# Soldering_Iron_V2.net
KiCad netlist of a schematic drawn in EAGLE
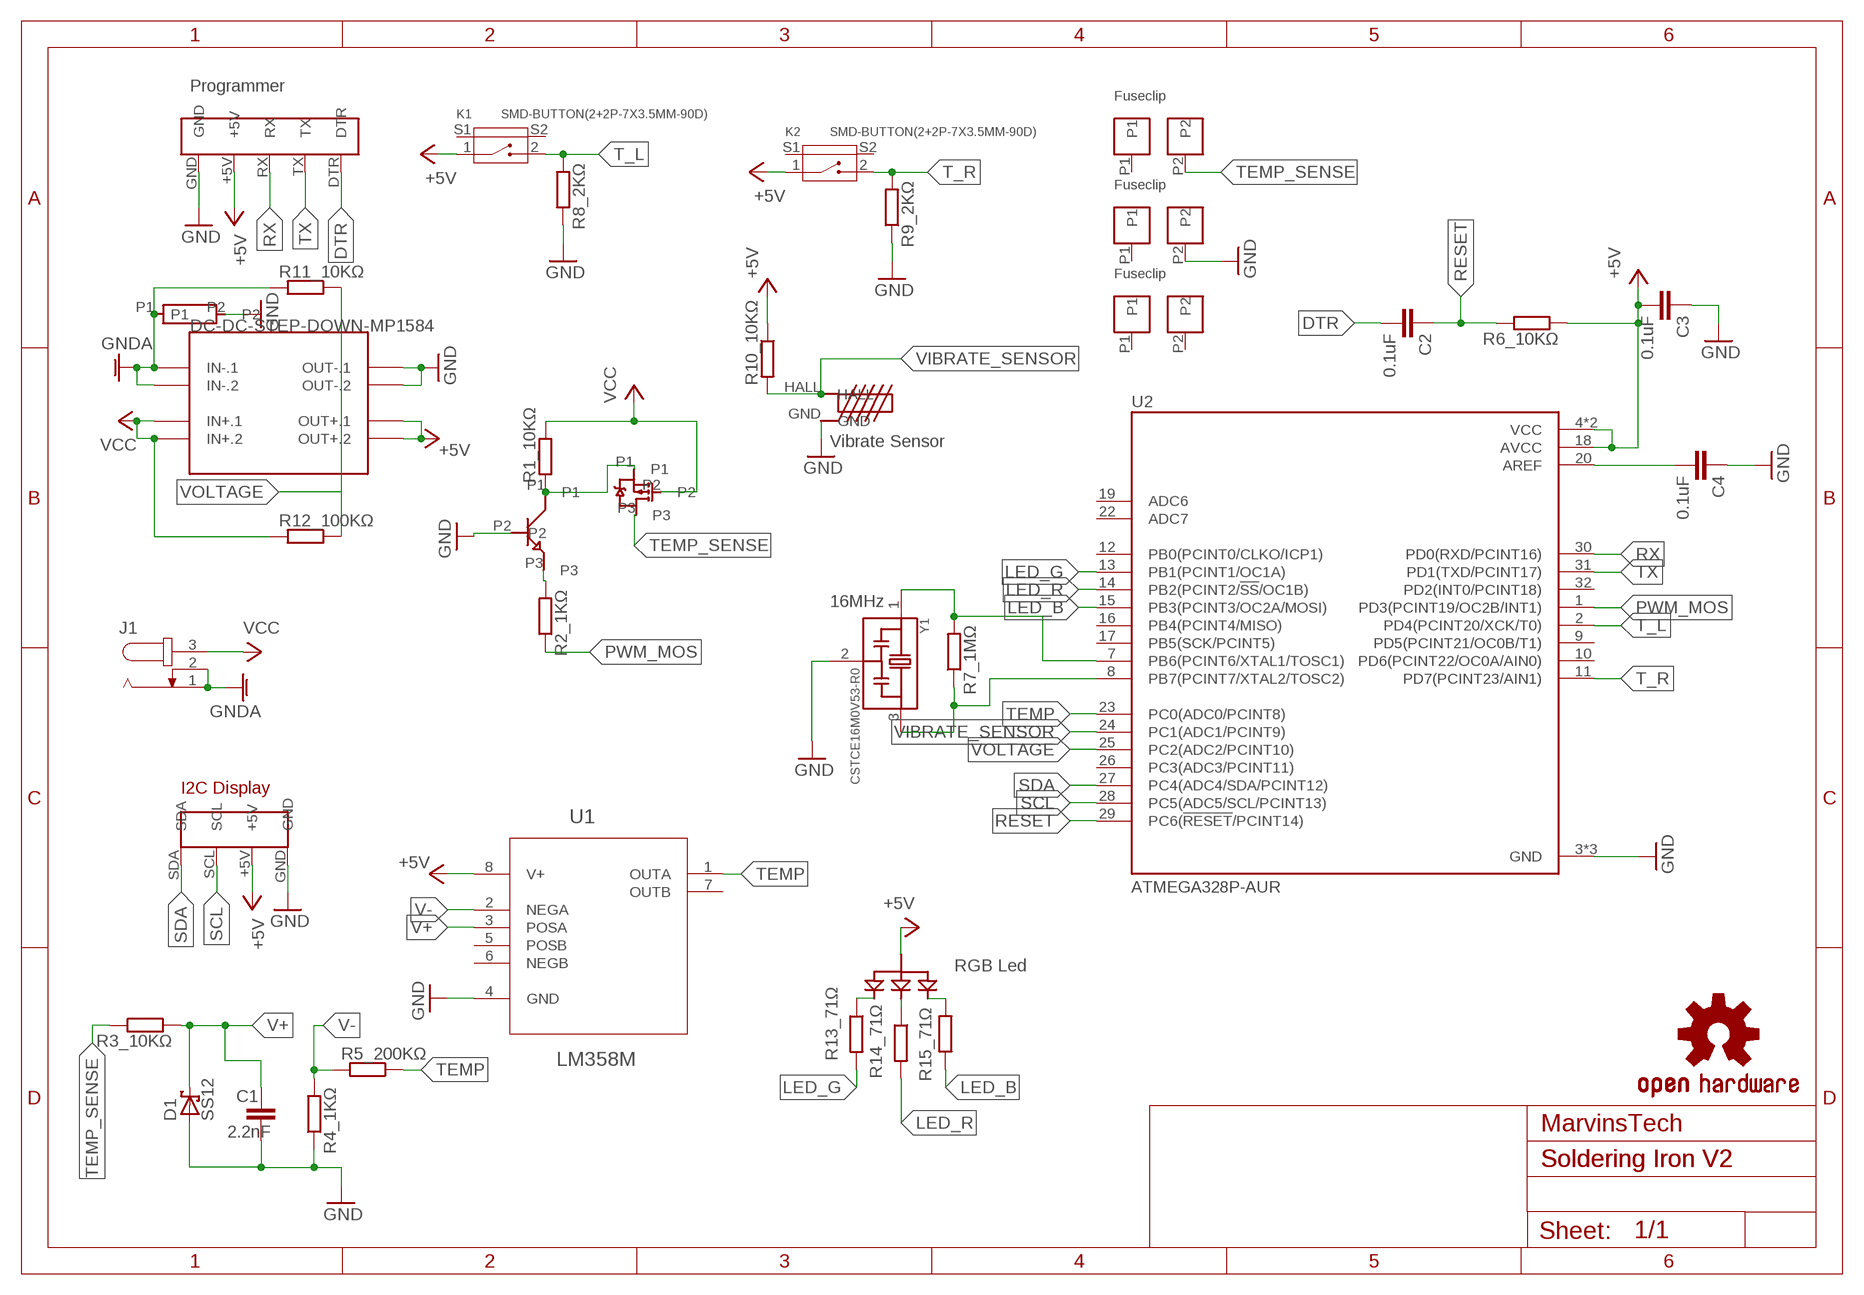
[diagram p0: schematic, sheet 1]

(export (version "E")
  (design (tool "Eeschema 10.0.6"))
  (components
    (comp (ref "C1")
      (value "2.2nF")
      (footprint "eagle-import:0603")
      (libsource (lib "eagle-import") (part "2.2NF/2200PF-0603-50V-10%"))
    )
    (comp (ref "C2")
      (value "0.1uF")
      (footprint "eagle-import:0603")
      (libsource (lib "eagle-import") (part "0.1UF-0603-25V-(+80/-20%)"))
    )
    (comp (ref "C3")
      (value "0.1uF")
      (footprint "eagle-import:0603")
      (libsource (lib "eagle-import") (part "0.1UF-0603-25V-(+80/-20%)"))
    )
    (comp (ref "C4")
      (value "0.1uF")
      (footprint "eagle-import:0603")
      (libsource (lib "eagle-import") (part "0.1UF-0603-25V-(+80/-20%)"))
    )
    (comp (ref "D1")
      (value "SS12")
      (footprint "eagle-import:DO214AC")
      (fields (field (name "MF") "Klein Tools,"))
      (libsource (lib "eagle-import") (part "SS12"))
    )
    (comp (ref "J1")
      (value "JACK-PLUG0")
      (footprint "eagle-import:SPC4077")
      (libsource (lib "eagle-import") (part "JACK-PLUG0"))
    )
    (comp (ref "K1")
      (value "SMD-BUTTON(2+2P-7X3.5MM-90D)")
      (footprint "eagle-import:SW4-SMD-7.0X3.5X3.5MM-90D")
      (fields (field (name "MF") "Best Inc.") (field (name "MP") "TS-1188E"))
      (libsource (lib "eagle-import") (part "SMD-BUTTON(2+2P-7X3.5MM-90D)"))
    )
    (comp (ref "K2")
      (value "SMD-BUTTON(2+2P-7X3.5MM-90D)")
      (footprint "eagle-import:SW4-SMD-7.0X3.5X3.5MM-90D")
      (fields (field (name "MF") "Best Inc.") (field (name "MP") "TS-1188E"))
      (libsource (lib "eagle-import") (part "SMD-BUTTON(2+2P-7X3.5MM-90D)"))
    )
    (comp (ref "R1_10KΩ")
      (value "SMK")
      (footprint "eagle-import:SMK")
      (libsource (lib "eagle-import") (part "SMK"))
    )
    (comp (ref "R2_1KΩ")
      (value "SMK")
      (footprint "eagle-import:SMK")
      (libsource (lib "eagle-import") (part "SMK"))
    )
    (comp (ref "R3_10KΩ")
      (value "SMK")
      (footprint "eagle-import:SMK")
      (libsource (lib "eagle-import") (part "SMK"))
    )
    (comp (ref "R4_1KΩ")
      (value "SMK")
      (footprint "eagle-import:SMK")
      (libsource (lib "eagle-import") (part "SMK"))
    )
    (comp (ref "R5_200KΩ")
      (value "SMK")
      (footprint "eagle-import:SMK")
      (libsource (lib "eagle-import") (part "SMK"))
    )
    (comp (ref "R6_10KΩ")
      (value "SMK")
      (footprint "eagle-import:SMK")
      (libsource (lib "eagle-import") (part "SMK"))
    )
    (comp (ref "R7_1MΩ")
      (value "SMK")
      (footprint "eagle-import:SMK")
      (libsource (lib "eagle-import") (part "SMK"))
    )
    (comp (ref "R8_2KΩ")
      (value "SMK")
      (footprint "eagle-import:SMK")
      (libsource (lib "eagle-import") (part "SMK"))
    )
    (comp (ref "R9_2KΩ")
      (value "SMK")
      (footprint "eagle-import:SMK")
      (libsource (lib "eagle-import") (part "SMK"))
    )
    (comp (ref "R10_10KΩ")
      (value "SMK")
      (footprint "eagle-import:SMK")
      (libsource (lib "eagle-import") (part "SMK"))
    )
    (comp (ref "R11_10KΩ")
      (value "SMK")
      (footprint "eagle-import:SMK")
      (libsource (lib "eagle-import") (part "SMK"))
    )
    (comp (ref "R12_100KΩ")
      (value "SMK")
      (footprint "eagle-import:SMK")
      (libsource (lib "eagle-import") (part "SMK"))
    )
    (comp (ref "R13_71Ω")
      (value "SMK")
      (footprint "eagle-import:SMK")
      (libsource (lib "eagle-import") (part "SMK"))
    )
    (comp (ref "R14_71Ω")
      (value "SMK")
      (footprint "eagle-import:SMK")
      (libsource (lib "eagle-import") (part "SMK"))
    )
    (comp (ref "R15_71Ω")
      (value "SMK")
      (footprint "eagle-import:SMK")
      (libsource (lib "eagle-import") (part "SMK"))
    )
    (comp (ref "U$1")
      (value "DC-DC-STEP-DOWN-MP1584")
      (footprint "eagle-import:DC-DC-STEP-DOWN-MP1584")
      (libsource (lib "eagle-import") (part "DC-DC-STEP-DOWN-MP1584"))
    )
    (comp (ref "U$2")
      (value "IRF4905STRLPBF")
      (footprint "eagle-import:D2PAK-5")
      (libsource (lib "eagle-import") (part "IRF4905STRLPBF"))
    )
    (comp (ref "U$3")
      (value "2SC3356NPNBJT")
      (footprint "eagle-import:TO236")
      (libsource (lib "eagle-import") (part "2SC3356NPNBJT"))
    )
    (comp (ref "U$4")
      (value "I2C_DISPLAY")
      (footprint "eagle-import:I2C_DISPLAY")
      (libsource (lib "eagle-import") (part "I2C_DISPLAY"))
    )
    (comp (ref "U$5")
      (value "VIBRATESENSOR")
      (footprint "eagle-import:VIBRATESENSOR")
      (libsource (lib "eagle-import") (part "VIBRATESENSOR"))
    )
    (comp (ref "U$6")
      (value "FUSECLIPS")
      (footprint "eagle-import:FUSECLIP")
      (libsource (lib "eagle-import") (part "FUSECLIPS"))
    )
    (comp (ref "U$7")
      (value "FUSECLIPS")
      (footprint "eagle-import:FUSECLIP")
      (libsource (lib "eagle-import") (part "FUSECLIPS"))
    )
    (comp (ref "U$8")
      (value "FUSECLIPS")
      (footprint "eagle-import:FUSECLIP")
      (libsource (lib "eagle-import") (part "FUSECLIPS"))
    )
    (comp (ref "U$9")
      (value "SHUNT_RESISTOR1")
      (footprint "eagle-import:RESISTOR1")
      (libsource (lib "eagle-import") (part "SHUNT_RESISTOR1"))
    )
    (comp (ref "U$10")
      (value "RGBLED")
      (footprint "eagle-import:RGBLED")
      (libsource (lib "eagle-import") (part "RGBLED"))
    )
    (comp (ref "U$11")
      (value "PROGRAMMER")
      (footprint "eagle-import:PROGRAMMER")
      (libsource (lib "eagle-import") (part "PROGRAMMER"))
    )
    (comp (ref "U$15")
      (value "OSHW-LOGOS")
      (footprint "eagle-import:OSHW-LOGO-S")
      (libsource (lib "eagle-import") (part "OSHW-LOGOS"))
    )
    (comp (ref "U1")
      (value "LM358M")
      (footprint "eagle-import:SOIC127P620X175-8N")
      (fields (field (name "MF") "ON Semiconductor"))
      (libsource (lib "eagle-import") (part "LM358M"))
    )
    (comp (ref "U2")
      (value "ATMEGA328P-AUR")
      (footprint "eagle-import:QFP80P900X900X120-32N")
      (fields (field (name "MF") "Microchip"))
      (libsource (lib "eagle-import") (part "ATMEGA328P-AUR"))
    )
    (comp (ref "Y1")
      (value "CSTCE16M0V53-R0")
      (footprint "eagle-import:OSC_CSTCE16M0V53-R0")
      (fields (field (name "MF") "Murata"))
      (libsource (lib "eagle-import") (part "CSTCE16M0V53-R0"))
    )
  )
  (nets
    (net (code "1") (name "+5V") (class "Default")
      (node (ref "C3") (pin "2") (pinfunction "2_2") (pintype "passive"))
      (node (ref "K1") (pin "1") (pinfunction "1_1") (pintype "bidirectional"))
      (node (ref "K2") (pin "1") (pinfunction "1_1") (pintype "bidirectional"))
      (node (ref "R10_10KΩ") (pin "1") (pinfunction "1_1") (pintype "passive"))
      (node (ref "R6_10KΩ") (pin "2") (pinfunction "2_2") (pintype "passive"))
      (node (ref "U$1") (pin "OUT+.1") (pinfunction "OUT+.1_OUT+.1") (pintype "bidirectional"))
      (node (ref "U$1") (pin "OUT+.2") (pinfunction "OUT+.2_OUT+.2") (pintype "bidirectional"))
      (node (ref "U$10") (pin "+5V") (pinfunction "+5V_+5V") (pintype "bidirectional"))
      (node (ref "U$11") (pin "+5V") (pinfunction "+5V_+5V") (pintype "bidirectional"))
      (node (ref "U$4") (pin "+5V") (pinfunction "+5V_+5V") (pintype "bidirectional"))
      (node (ref "U1") (pin "8") (pinfunction "V+_8") (pintype "power_in"))
      (node (ref "U2") (pin "18") (pinfunction "AVCC_18") (pintype "power_in"))
      (node (ref "U2") (pin "4") (pinfunction "VCC_4") (pintype "power_in"))
      (node (ref "U2") (pin "6") (pinfunction "VCC_6") (pintype "power_in"))
    )
    (net (code "2") (name "DTR") (class "Default")
      (node (ref "C2") (pin "2") (pinfunction "2_2") (pintype "passive"))
      (node (ref "U$11") (pin "DTR") (pinfunction "DTR_DTR") (pintype "bidirectional"))
    )
    (net (code "3") (name "GND") (class "Default")
      (node (ref "C1") (pin "2") (pinfunction "2_2") (pintype "passive"))
      (node (ref "C3") (pin "1") (pinfunction "1_1") (pintype "passive"))
      (node (ref "C4") (pin "1") (pinfunction "1_1") (pintype "passive"))
      (node (ref "D1") (pin "A") (pinfunction "A_A") (pintype "passive"))
      (node (ref "R4_1KΩ") (pin "1") (pinfunction "1_1") (pintype "passive"))
      (node (ref "R8_2KΩ") (pin "1") (pinfunction "1_1") (pintype "passive"))
      (node (ref "R9_2KΩ") (pin "1") (pinfunction "1_1") (pintype "passive"))
      (node (ref "U$1") (pin "OUT-.1") (pinfunction "OUT-.1_OUT-.1") (pintype "bidirectional"))
      (node (ref "U$1") (pin "OUT-.2") (pinfunction "OUT-.2_OUT-.2") (pintype "bidirectional"))
      (node (ref "U$11") (pin "GND") (pinfunction "GND_GND") (pintype "bidirectional"))
      (node (ref "U$3") (pin "P2") (pinfunction "P2_P2") (pintype "bidirectional"))
      (node (ref "U$4") (pin "GND") (pinfunction "GND_GND") (pintype "bidirectional"))
      (node (ref "U$5") (pin "GND") (pinfunction "GND_GND") (pintype "bidirectional"))
      (node (ref "U$7") (pin "P2") (pinfunction "P2_P2") (pintype "bidirectional"))
      (node (ref "U$9") (pin "P2") (pinfunction "P2_P2") (pintype "bidirectional"))
      (node (ref "U1") (pin "4") (pinfunction "GND_4") (pintype "passive"))
      (node (ref "U2") (pin "21") (pinfunction "GND_21") (pintype "power_in"))
      (node (ref "U2") (pin "3") (pinfunction "GND_3") (pintype "power_in"))
      (node (ref "U2") (pin "5") (pinfunction "GND_5") (pintype "power_in"))
      (node (ref "Y1") (pin "2") (pinfunction "2_2") (pintype "power_in"))
    )
    (net (code "4") (name "GNDA") (class "Default")
      (node (ref "J1") (pin "1") (pinfunction "1_1") (pintype "passive"))
      (node (ref "J1") (pin "2") (pinfunction "2_2") (pintype "passive"))
      (node (ref "R11_10KΩ") (pin "2") (pinfunction "2_2") (pintype "passive"))
      (node (ref "U$1") (pin "IN-.1") (pinfunction "IN-.1_IN-.1") (pintype "bidirectional"))
      (node (ref "U$1") (pin "IN-.2") (pinfunction "IN-.2_IN-.2") (pintype "bidirectional"))
      (node (ref "U$9") (pin "P1") (pinfunction "P1_P1") (pintype "bidirectional"))
    )
    (net (code "5") (name "LED_B") (class "Default")
      (node (ref "R15_71Ω") (pin "1") (pinfunction "1_1") (pintype "passive"))
      (node (ref "U2") (pin "15") (pinfunction "PB3(PCINT3/OC2A/MOSI)_15") (pintype "bidirectional"))
    )
    (net (code "6") (name "LED_G") (class "Default")
      (node (ref "R13_71Ω") (pin "2") (pinfunction "2_2") (pintype "passive"))
      (node (ref "U2") (pin "13") (pinfunction "PB1(PCINT1/OC1A)_13") (pintype "bidirectional"))
    )
    (net (code "7") (name "LED_R") (class "Default")
      (node (ref "R14_71Ω") (pin "2") (pinfunction "2_2") (pintype "passive"))
      (node (ref "U2") (pin "14") (pinfunction "PB2(PCINT2/~{SS}/OC1B)_14") (pintype "bidirectional"))
    )
    (net (code "8") (name "Net-(R1_10KΩ-Pad2)") (class "Default")
      (node (ref "R1_10KΩ") (pin "2") (pinfunction "2_2") (pintype "passive"))
      (node (ref "U$2") (pin "P1") (pinfunction "P1_P1") (pintype "bidirectional"))
      (node (ref "U$3") (pin "P1") (pinfunction "P1_P1") (pintype "bidirectional"))
    )
    (net (code "9") (name "Net-(R2_1KΩ-Pad2)") (class "Default")
      (node (ref "R2_1KΩ") (pin "2") (pinfunction "2_2") (pintype "passive"))
      (node (ref "U$3") (pin "P3") (pinfunction "P3_P3") (pintype "bidirectional"))
    )
    (net (code "10") (name "Net-(R13_71Ω-Pad1)") (class "Default")
      (node (ref "R13_71Ω") (pin "1") (pinfunction "1_1") (pintype "passive"))
      (node (ref "U$10") (pin "P3") (pinfunction "P3_P3") (pintype "bidirectional"))
    )
    (net (code "11") (name "Net-(R14_71Ω-Pad1)") (class "Default")
      (node (ref "R14_71Ω") (pin "1") (pinfunction "1_1") (pintype "passive"))
      (node (ref "U$10") (pin "P2") (pinfunction "P2_P2") (pintype "bidirectional"))
    )
    (net (code "12") (name "Net-(R15_71Ω-Pad2)") (class "Default")
      (node (ref "R15_71Ω") (pin "2") (pinfunction "2_2") (pintype "passive"))
      (node (ref "U$10") (pin "P1") (pinfunction "P1_P1") (pintype "bidirectional"))
    )
    (net (code "13") (name "Net-(U2-AREF)") (class "Default")
      (node (ref "C4") (pin "2") (pinfunction "2_2") (pintype "passive"))
      (node (ref "U2") (pin "20") (pinfunction "AREF_20") (pintype "power_in"))
    )
    (net (code "14") (name "Net-(U2-PB6(PCINT6{slash}XTAL1{slash}TOSC1))") (class "Default")
      (node (ref "R7_1MΩ") (pin "2") (pinfunction "2_2") (pintype "passive"))
      (node (ref "U2") (pin "7") (pinfunction "PB6(PCINT6/XTAL1/TOSC1)_7") (pintype "bidirectional"))
      (node (ref "Y1") (pin "1") (pinfunction "1_1") (pintype "passive"))
    )
    (net (code "15") (name "Net-(U2-PB7(PCINT7{slash}XTAL2{slash}TOSC2))") (class "Default")
      (node (ref "R7_1MΩ") (pin "1") (pinfunction "1_1") (pintype "passive"))
      (node (ref "U2") (pin "8") (pinfunction "PB7(PCINT7/XTAL2/TOSC2)_8") (pintype "bidirectional"))
      (node (ref "Y1") (pin "3") (pinfunction "3_3") (pintype "passive"))
    )
    (net (code "16") (name "PWM_MOS") (class "Default")
      (node (ref "R2_1KΩ") (pin "1") (pinfunction "1_1") (pintype "passive"))
      (node (ref "U2") (pin "1") (pinfunction "PD3(PCINT19/OC2B/INT1)_1") (pintype "bidirectional"))
    )
    (net (code "17") (name "RESET") (class "Default")
      (node (ref "C2") (pin "1") (pinfunction "1_1") (pintype "passive"))
      (node (ref "R6_10KΩ") (pin "1") (pinfunction "1_1") (pintype "passive"))
      (node (ref "U2") (pin "29") (pinfunction "PC6(~{RESET}/PCINT14)_29") (pintype "bidirectional"))
    )
    (net (code "18") (name "RX") (class "Default")
      (node (ref "U$11") (pin "RX") (pinfunction "RX_RX") (pintype "bidirectional"))
      (node (ref "U2") (pin "30") (pinfunction "PD0(RXD/PCINT16)_30") (pintype "bidirectional"))
    )
    (net (code "19") (name "SCL") (class "Default")
      (node (ref "U$4") (pin "SCL") (pinfunction "SCL_SCL") (pintype "bidirectional"))
      (node (ref "U2") (pin "28") (pinfunction "PC5(ADC5/SCL/PCINT13)_28") (pintype "bidirectional"))
    )
    (net (code "20") (name "SDA") (class "Default")
      (node (ref "U$4") (pin "SDA") (pinfunction "SDA_SDA") (pintype "bidirectional"))
      (node (ref "U2") (pin "27") (pinfunction "PC4(ADC4/SDA/PCINT12)_27") (pintype "bidirectional"))
    )
    (net (code "21") (name "TEMP") (class "Default")
      (node (ref "R5_200KΩ") (pin "1") (pinfunction "1_1") (pintype "passive"))
      (node (ref "U1") (pin "1") (pinfunction "OUTA_1") (pintype "output"))
      (node (ref "U2") (pin "23") (pinfunction "PC0(ADC0/PCINT8)_23") (pintype "bidirectional"))
    )
    (net (code "22") (name "TEMP_SENSE") (class "Default")
      (node (ref "R3_10KΩ") (pin "1") (pinfunction "1_1") (pintype "passive"))
      (node (ref "U$2") (pin "P3") (pinfunction "P3_P3") (pintype "bidirectional"))
      (node (ref "U$6") (pin "P2") (pinfunction "P2_P2") (pintype "bidirectional"))
    )
    (net (code "23") (name "TX") (class "Default")
      (node (ref "U$11") (pin "TX") (pinfunction "TX_TX") (pintype "bidirectional"))
      (node (ref "U2") (pin "31") (pinfunction "PD1(TXD/PCINT17)_31") (pintype "bidirectional"))
    )
    (net (code "24") (name "T_L") (class "Default")
      (node (ref "K1") (pin "2") (pinfunction "2_2") (pintype "bidirectional"))
      (node (ref "R8_2KΩ") (pin "2") (pinfunction "2_2") (pintype "passive"))
      (node (ref "U2") (pin "2") (pinfunction "PD4(PCINT20/XCK/T0)_2") (pintype "bidirectional"))
    )
    (net (code "25") (name "T_R") (class "Default")
      (node (ref "K2") (pin "2") (pinfunction "2_2") (pintype "bidirectional"))
      (node (ref "R9_2KΩ") (pin "2") (pinfunction "2_2") (pintype "passive"))
      (node (ref "U2") (pin "11") (pinfunction "PD7(PCINT23/AIN1)_11") (pintype "bidirectional"))
    )
    (net (code "26") (name "V+") (class "Default")
      (node (ref "C1") (pin "1") (pinfunction "1_1") (pintype "passive"))
      (node (ref "D1") (pin "C") (pinfunction "C_C") (pintype "passive"))
      (node (ref "R3_10KΩ") (pin "2") (pinfunction "2_2") (pintype "passive"))
      (node (ref "U1") (pin "3") (pinfunction "POSA_3") (pintype "input"))
    )
    (net (code "27") (name "V-") (class "Default")
      (node (ref "R4_1KΩ") (pin "2") (pinfunction "2_2") (pintype "passive"))
      (node (ref "R5_200KΩ") (pin "2") (pinfunction "2_2") (pintype "passive"))
      (node (ref "U1") (pin "2") (pinfunction "NEGA_2") (pintype "input"))
    )
    (net (code "28") (name "VCC") (class "Default")
      (node (ref "J1") (pin "3") (pinfunction "3_3") (pintype "passive"))
      (node (ref "R12_100KΩ") (pin "2") (pinfunction "2_2") (pintype "passive"))
      (node (ref "R1_10KΩ") (pin "1") (pinfunction "1_1") (pintype "passive"))
      (node (ref "U$1") (pin "IN+.1") (pinfunction "IN+.1_IN+.1") (pintype "bidirectional"))
      (node (ref "U$1") (pin "IN+.2") (pinfunction "IN+.2_IN+.2") (pintype "bidirectional"))
      (node (ref "U$2") (pin "P2") (pinfunction "P2_P2") (pintype "bidirectional"))
    )
    (net (code "29") (name "VIBRATE_SENSOR") (class "Default")
      (node (ref "R10_10KΩ") (pin "2") (pinfunction "2_2") (pintype "passive"))
      (node (ref "U$5") (pin "HALL") (pinfunction "HALL_HALL") (pintype "bidirectional"))
      (node (ref "U2") (pin "24") (pinfunction "PC1(ADC1/PCINT9)_24") (pintype "bidirectional"))
    )
    (net (code "30") (name "VOLTAGE") (class "Default")
      (node (ref "R11_10KΩ") (pin "1") (pinfunction "1_1") (pintype "passive"))
      (node (ref "R12_100KΩ") (pin "1") (pinfunction "1_1") (pintype "passive"))
      (node (ref "U2") (pin "25") (pinfunction "PC2(ADC2/PCINT10)_25") (pintype "bidirectional"))
    )
    (net (code "31") (name "unconnected-(K1-PadS1)") (class "Default")
      (node (ref "K1") (pin "S1") (pinfunction "S1_S1") (pintype "bidirectional"))
    )
    (net (code "32") (name "unconnected-(K1-PadS2)") (class "Default")
      (node (ref "K1") (pin "S2") (pinfunction "S2_S2") (pintype "bidirectional"))
    )
    (net (code "33") (name "unconnected-(K2-PadS1)") (class "Default")
      (node (ref "K2") (pin "S1") (pinfunction "S1_S1") (pintype "bidirectional"))
    )
    (net (code "34") (name "unconnected-(K2-PadS2)") (class "Default")
      (node (ref "K2") (pin "S2") (pinfunction "S2_S2") (pintype "bidirectional"))
    )
    (net (code "35") (name "unconnected-(U$6-PadP1)") (class "Default")
      (node (ref "U$6") (pin "P1") (pinfunction "P1_P1") (pintype "bidirectional"))
    )
    (net (code "36") (name "unconnected-(U$7-PadP1)") (class "Default")
      (node (ref "U$7") (pin "P1") (pinfunction "P1_P1") (pintype "bidirectional"))
    )
    (net (code "37") (name "unconnected-(U$8-PadP1)") (class "Default")
      (node (ref "U$8") (pin "P1") (pinfunction "P1_P1") (pintype "bidirectional"))
    )
    (net (code "38") (name "unconnected-(U$8-PadP2)") (class "Default")
      (node (ref "U$8") (pin "P2") (pinfunction "P2_P2") (pintype "bidirectional"))
    )
    (net (code "39") (name "unconnected-(U1-NEGB-Pad6)") (class "Default")
      (node (ref "U1") (pin "6") (pinfunction "NEGB_6") (pintype "input"))
    )
    (net (code "40") (name "unconnected-(U1-OUTB-Pad7)") (class "Default")
      (node (ref "U1") (pin "7") (pinfunction "OUTB_7") (pintype "output"))
    )
    (net (code "41") (name "unconnected-(U1-POSB-Pad5)") (class "Default")
      (node (ref "U1") (pin "5") (pinfunction "POSB_5") (pintype "input"))
    )
    (net (code "42") (name "unconnected-(U2-ADC6-Pad19)") (class "Default")
      (node (ref "U2") (pin "19") (pinfunction "ADC6_19") (pintype "input"))
    )
    (net (code "43") (name "unconnected-(U2-ADC7-Pad22)") (class "Default")
      (node (ref "U2") (pin "22") (pinfunction "ADC7_22") (pintype "input"))
    )
    (net (code "44") (name "unconnected-(U2-PB0(PCINT0{slash}CLKO{slash}ICP1)-Pad12)") (class "Default")
      (node (ref "U2") (pin "12") (pinfunction "PB0(PCINT0/CLKO/ICP1)_12") (pintype "bidirectional"))
    )
    (net (code "45") (name "unconnected-(U2-PB4(PCINT4{slash}MISO)-Pad16)") (class "Default")
      (node (ref "U2") (pin "16") (pinfunction "PB4(PCINT4/MISO)_16") (pintype "bidirectional"))
    )
    (net (code "46") (name "unconnected-(U2-PB5(SCK{slash}PCINT5)-Pad17)") (class "Default")
      (node (ref "U2") (pin "17") (pinfunction "PB5(SCK/PCINT5)_17") (pintype "bidirectional"))
    )
    (net (code "47") (name "unconnected-(U2-PC3(ADC3{slash}PCINT11)-Pad26)") (class "Default")
      (node (ref "U2") (pin "26") (pinfunction "PC3(ADC3/PCINT11)_26") (pintype "bidirectional"))
    )
    (net (code "48") (name "unconnected-(U2-PD2(INT0{slash}PCINT18)-Pad32)") (class "Default")
      (node (ref "U2") (pin "32") (pinfunction "PD2(INT0/PCINT18)_32") (pintype "bidirectional"))
    )
    (net (code "49") (name "unconnected-(U2-PD5(PCINT21{slash}OC0B{slash}T1)-Pad9)") (class "Default")
      (node (ref "U2") (pin "9") (pinfunction "PD5(PCINT21/OC0B/T1)_9") (pintype "bidirectional"))
    )
    (net (code "50") (name "unconnected-(U2-PD6(PCINT22{slash}OC0A{slash}AIN0)-Pad10)") (class "Default")
      (node (ref "U2") (pin "10") (pinfunction "PD6(PCINT22/OC0A/AIN0)_10") (pintype "bidirectional"))
    )
  )
)
